# Zobo.net
KiCad netlist of a schematic drawn in EAGLE
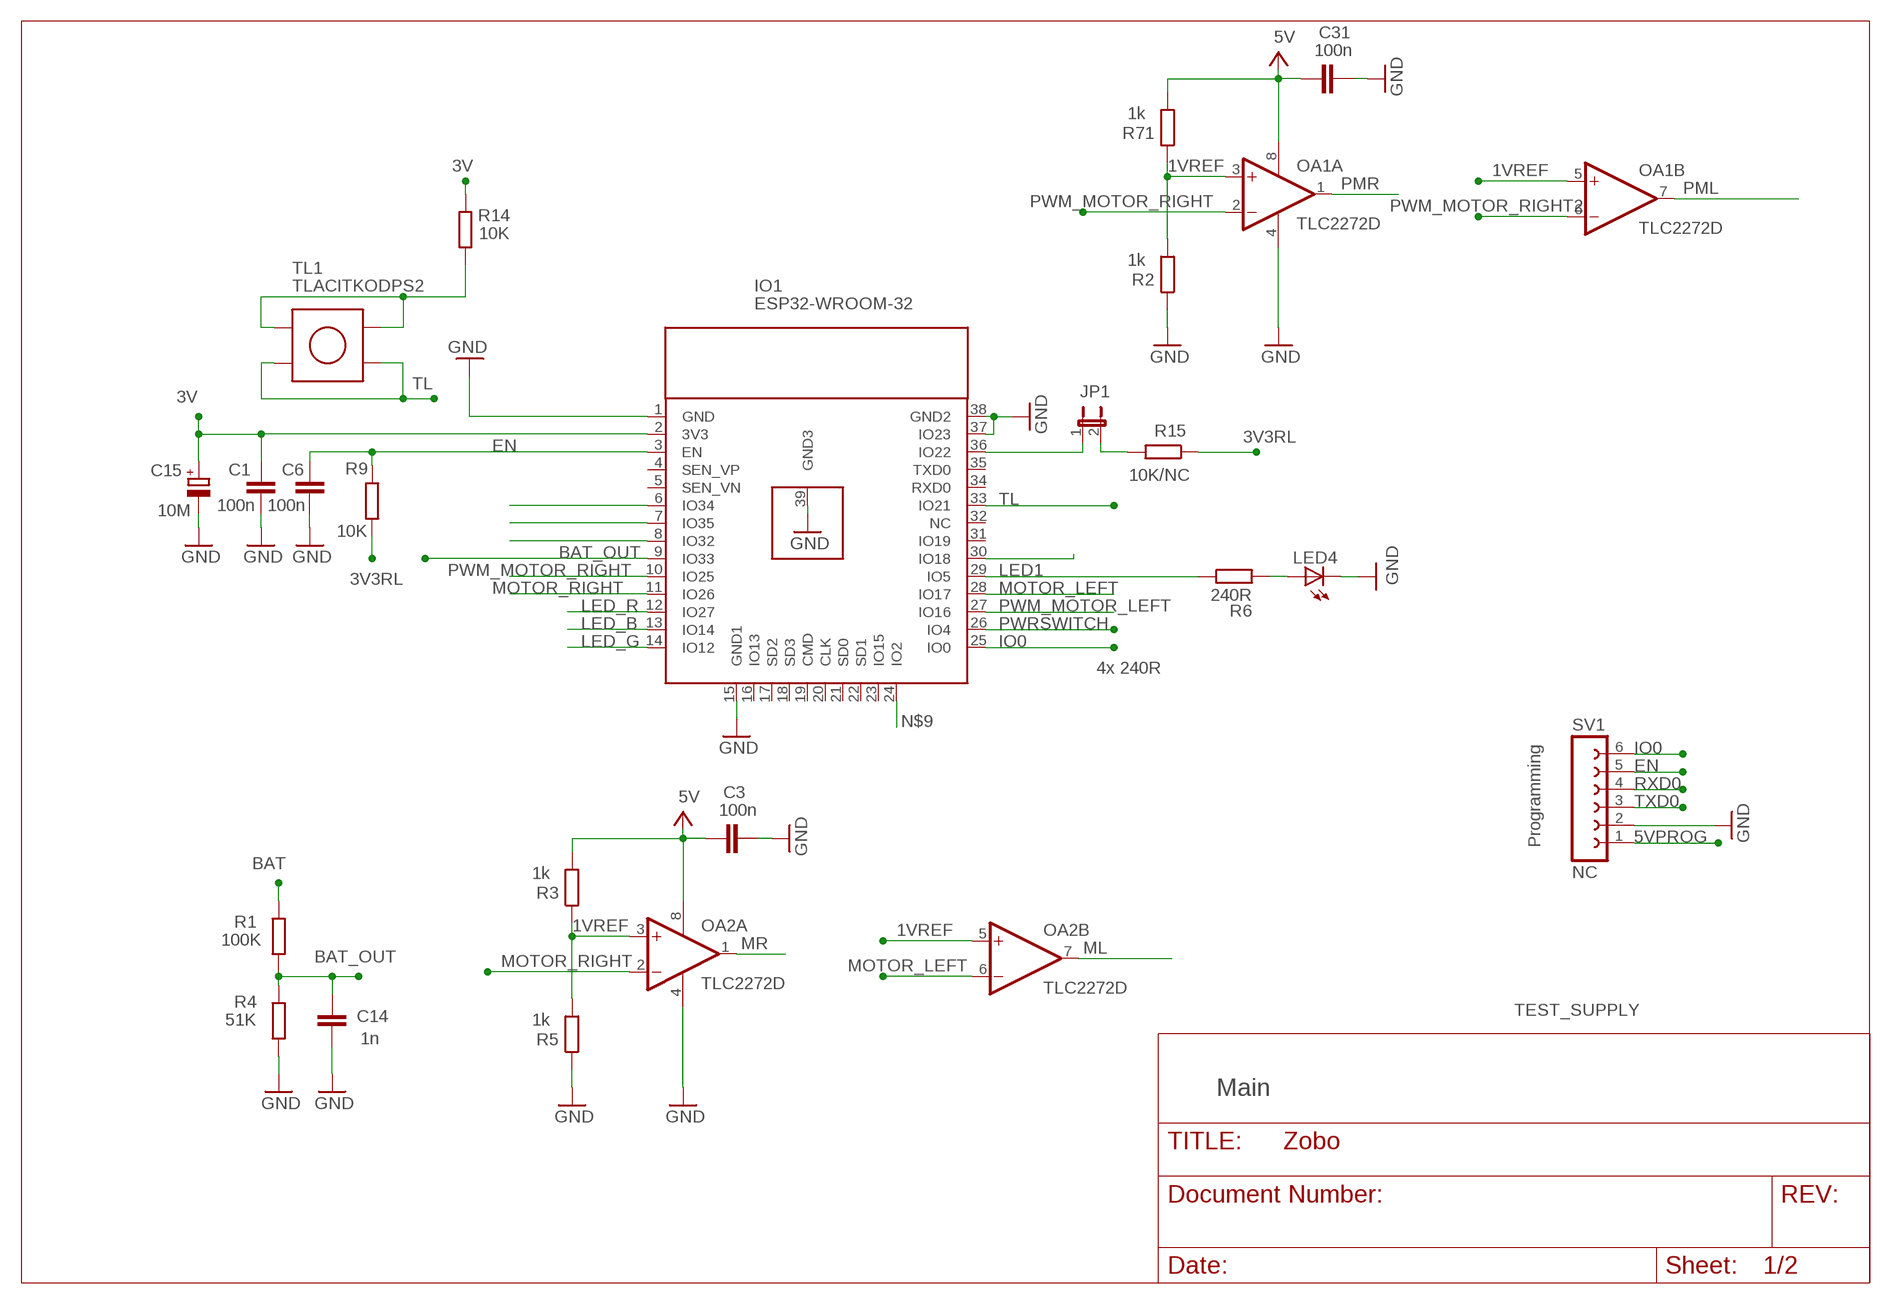
[diagram p0: schematic, sheet 1]
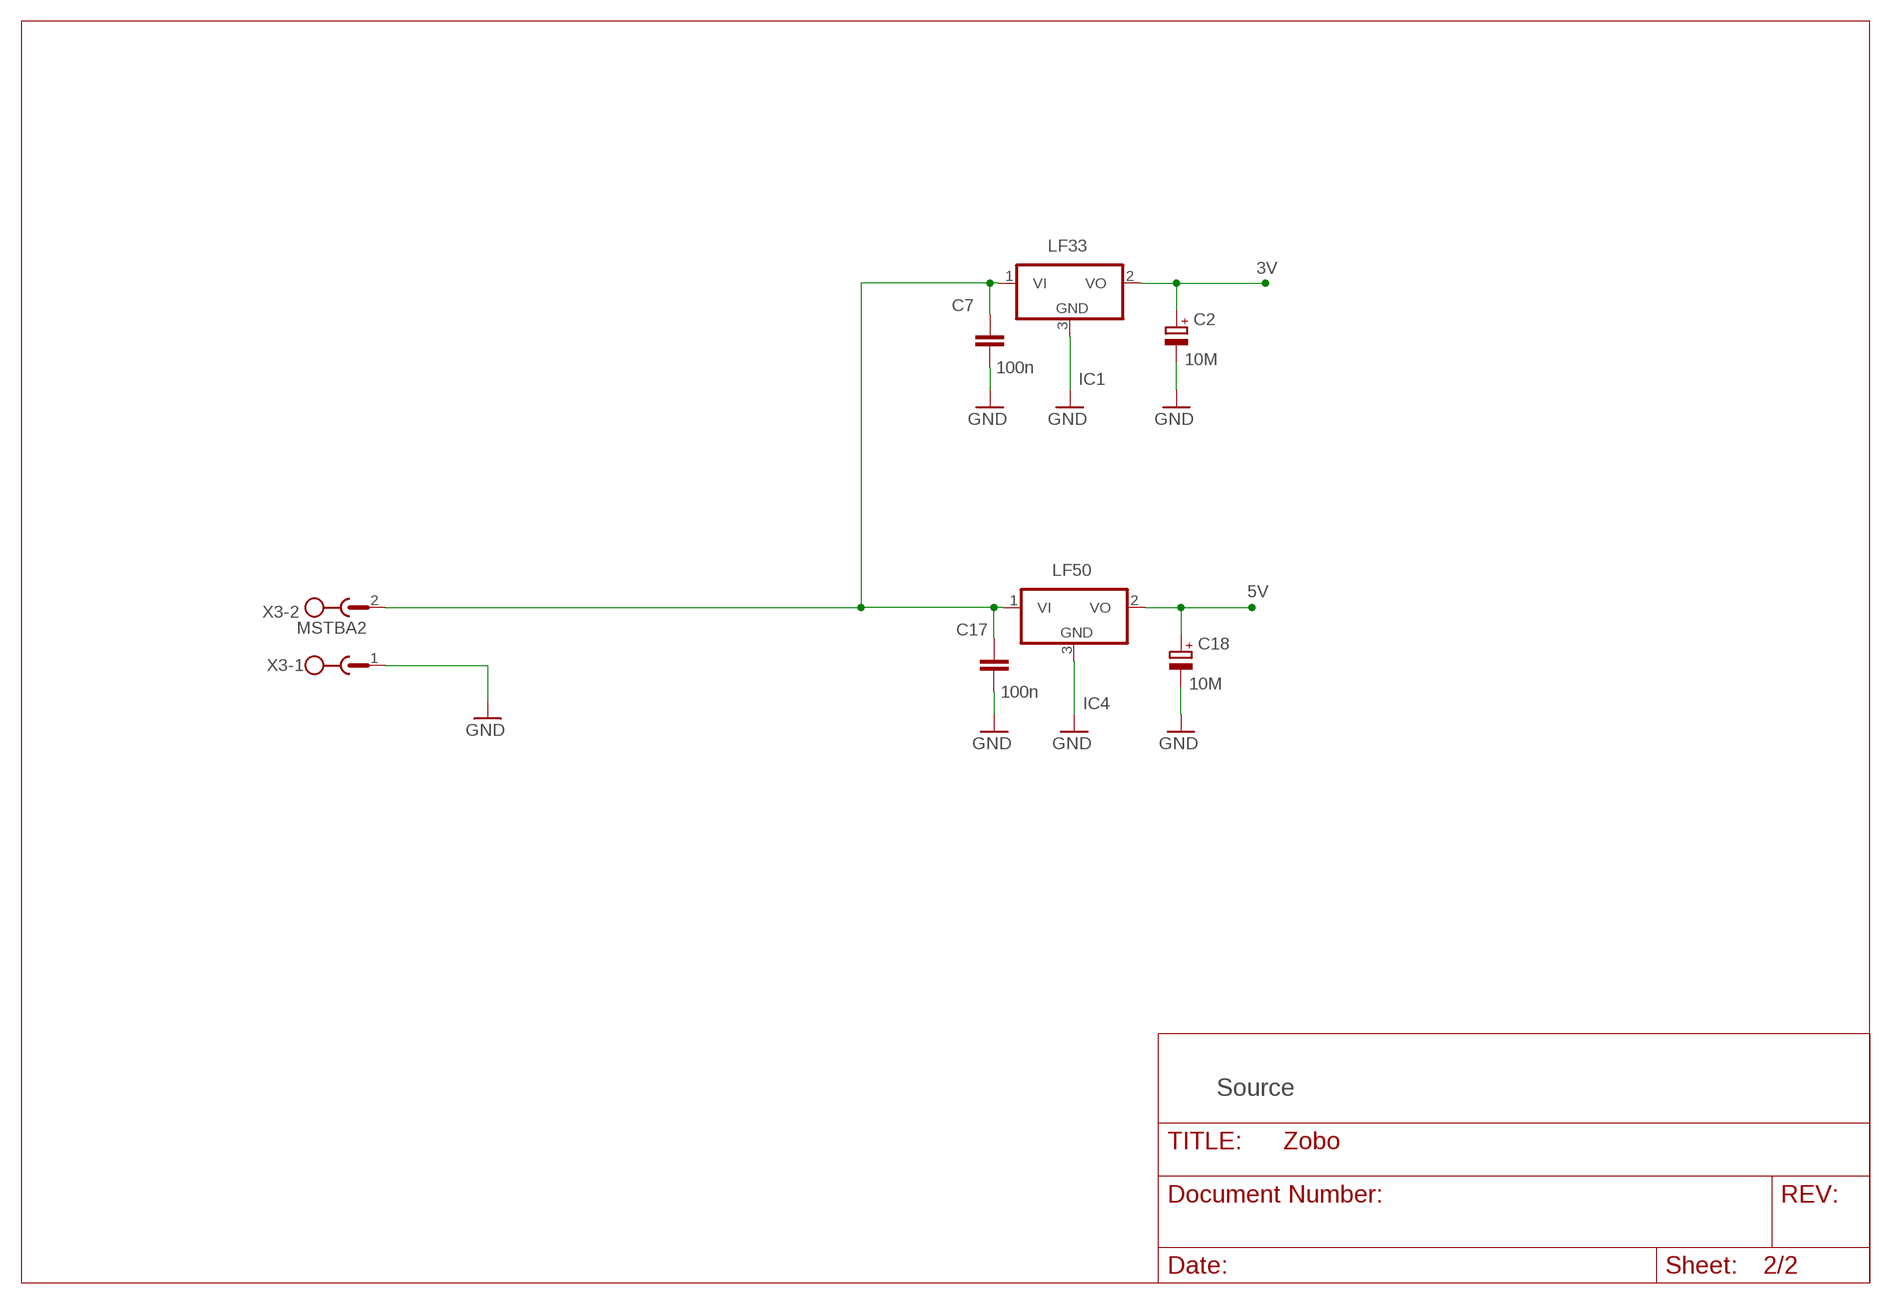
[diagram p1: schematic, sheet 2]

(export (version "E")
  (design (tool "Eeschema 10.0.6"))
  (components
    (comp (ref "C2")
      (value "10M")
      (footprint "eagle-import:CT3216")
      (libsource (lib "eagle-import") (part "CPOL-EUCT3216"))
    )
    (comp (ref "C7")
      (value "100n")
      (footprint "eagle-import:C0805")
      (libsource (lib "eagle-import") (part "C-EUC0805"))
    )
    (comp (ref "C17")
      (value "100n")
      (footprint "eagle-import:C0805")
      (libsource (lib "eagle-import") (part "C-EUC0805"))
    )
    (comp (ref "C18")
      (value "10M")
      (footprint "eagle-import:CT3216")
      (libsource (lib "eagle-import") (part "CPOL-EUCT3216"))
    )
    (comp (ref "IC1")
      (value "LF33")
      (footprint "eagle-import:TO252")
      (libsource (lib "eagle-import") (part "78DT05"))
    )
    (comp (ref "IC4")
      (value "LF50")
      (footprint "eagle-import:TO252")
      (libsource (lib "eagle-import") (part "78DT05"))
    )
    (comp (ref "X3")
      (value "MSTBA2")
      (footprint "eagle-import:MSTBA2")
      (fields (field (name "MF") "FARNELL") (field (name "MPN") "1757242"))
      (libsource (lib "eagle-import") (part "MSTBA2"))
    )
    (comp (ref "C1")
      (value "100n")
      (footprint "eagle-import:C0805")
      (libsource (lib "eagle-import") (part "C-EUC0805"))
    )
    (comp (ref "C3")
      (value "100n")
      (footprint "eagle-import:C0805")
      (libsource (lib "eagle-import") (part "rcl_TOM_C-EUC0805"))
    )
    (comp (ref "C6")
      (value "100n")
      (footprint "eagle-import:C0805")
      (libsource (lib "eagle-import") (part "C-EUC0805"))
    )
    (comp (ref "C14")
      (value "1n")
      (footprint "eagle-import:C0805")
      (libsource (lib "eagle-import") (part "C-EUC0805"))
    )
    (comp (ref "C15")
      (value "10M")
      (footprint "eagle-import:CT3216")
      (libsource (lib "eagle-import") (part "CPOL-EUCT3216"))
    )
    (comp (ref "C31")
      (value "100n")
      (footprint "eagle-import:C0805")
      (libsource (lib "eagle-import") (part "rcl_TOM_C-EUC0805"))
    )
    (comp (ref "IO1")
      (value "ESP32-WROOM-32")
      (footprint "eagle-import:ESP32-WROOM-32")
      (libsource (lib "eagle-import") (part "ESP32-WROOM-32"))
    )
    (comp (ref "JP1")
      (value "JP1E")
      (footprint "eagle-import:JP1")
      (libsource (lib "eagle-import") (part "JP1E"))
    )
    (comp (ref "LED4")
      (value "LEDCHIPLED_0805")
      (footprint "eagle-import:CHIPLED_0805")
      (libsource (lib "eagle-import") (part "LEDCHIPLED_0805"))
    )
    (comp (ref "OA1")
      (value "TLC2272D")
      (footprint "eagle-import:SO08")
      (libsource (lib "eagle-import") (part "TLC2272D"))
    )
    (comp (ref "OA2")
      (value "TLC2272D")
      (footprint "eagle-import:SO08")
      (libsource (lib "eagle-import") (part "TLC2272D"))
    )
    (comp (ref "R1")
      (value "100K")
      (footprint "eagle-import:R0805")
      (libsource (lib "eagle-import") (part "R-EU_R0805"))
    )
    (comp (ref "R2")
      (value "1k")
      (footprint "eagle-import:R0805")
      (libsource (lib "eagle-import") (part "R-EU_R0805"))
    )
    (comp (ref "R3")
      (value "1k")
      (footprint "eagle-import:R0805")
      (libsource (lib "eagle-import") (part "R-EU_R0805"))
    )
    (comp (ref "R4")
      (value "51K")
      (footprint "eagle-import:R0805")
      (libsource (lib "eagle-import") (part "R-EU_R0805"))
    )
    (comp (ref "R5")
      (value "1k")
      (footprint "eagle-import:R0805")
      (libsource (lib "eagle-import") (part "R-EU_R0805"))
    )
    (comp (ref "R6")
      (value "240R")
      (footprint "eagle-import:R0805")
      (libsource (lib "eagle-import") (part "R-EU_R0805"))
    )
    (comp (ref "R9")
      (value "10K")
      (footprint "eagle-import:R0805")
      (libsource (lib "eagle-import") (part "R-EU_R0805"))
    )
    (comp (ref "R14")
      (value "10K")
      (footprint "eagle-import:R0805")
      (libsource (lib "eagle-import") (part "R-EU_R0805"))
    )
    (comp (ref "R15")
      (value "10K/NC")
      (footprint "eagle-import:R0805")
      (libsource (lib "eagle-import") (part "R-EU_R0805"))
    )
    (comp (ref "R71")
      (value "1k")
      (footprint "eagle-import:R0805")
      (libsource (lib "eagle-import") (part "R-EU_R0805"))
    )
    (comp (ref "SV1")
      (value "NC")
      (footprint "eagle-import:FE06")
      (libsource (lib "eagle-import") (part "FE06-1R"))
    )
    (comp (ref "TL1")
      (value "TLACITKODPS2")
      (footprint "eagle-import:TLACITKO_DPS2")
      (libsource (lib "eagle-import") (part "TLACITKO?DPS2"))
    )
  )
  (nets
    (net (code "1") (name "1VREF") (class "Default")
      (node (ref "OA1") (pin "3") (pinfunction "+IN_3") (pintype "input"))
      (node (ref "OA1") (pin "5") (pinfunction "+IN_5") (pintype "input"))
      (node (ref "OA2") (pin "3") (pinfunction "+IN_3") (pintype "input"))
      (node (ref "OA2") (pin "5") (pinfunction "+IN_5") (pintype "input"))
      (node (ref "R2") (pin "2") (pinfunction "2_2") (pintype "passive"))
      (node (ref "R3") (pin "1") (pinfunction "1_1") (pintype "passive"))
      (node (ref "R5") (pin "2") (pinfunction "2_2") (pintype "passive"))
      (node (ref "R71") (pin "1") (pinfunction "1_1") (pintype "passive"))
    )
    (net (code "2") (name "3V") (class "Default")
      (node (ref "C1") (pin "2") (pinfunction "2_2") (pintype "passive"))
      (node (ref "C15") (pin "+") (pinfunction "+_+") (pintype "passive"))
      (node (ref "C2") (pin "+") (pinfunction "+_+") (pintype "passive"))
      (node (ref "IC1") (pin "2") (pinfunction "VO_2") (pintype "passive"))
      (node (ref "IO1") (pin "2") (pinfunction "3V3_2") (pintype "passive"))
      (node (ref "R14") (pin "2") (pinfunction "2_2") (pintype "passive"))
    )
    (net (code "3") (name "3V3RL") (class "Default")
      (node (ref "R15") (pin "1") (pinfunction "1_1") (pintype "passive"))
      (node (ref "R9") (pin "2") (pinfunction "2_2") (pintype "passive"))
    )
    (net (code "4") (name "5V") (class "Default")
      (node (ref "C18") (pin "+") (pinfunction "+_+") (pintype "passive"))
      (node (ref "C3") (pin "1") (pinfunction "1_1") (pintype "passive"))
      (node (ref "C31") (pin "1") (pinfunction "1_1") (pintype "passive"))
      (node (ref "IC4") (pin "2") (pinfunction "VO_2") (pintype "passive"))
      (node (ref "OA1") (pin "8") (pinfunction "V+_8") (pintype "power_in"))
      (node (ref "OA2") (pin "8") (pinfunction "V+_8") (pintype "power_in"))
      (node (ref "R3") (pin "2") (pinfunction "2_2") (pintype "passive"))
      (node (ref "R71") (pin "2") (pinfunction "2_2") (pintype "passive"))
    )
    (net (code "5") (name "5VPROG") (class "Default")
      (node (ref "SV1") (pin "1") (pinfunction "1_1") (pintype "passive"))
    )
    (net (code "6") (name "BAT") (class "Default")
      (node (ref "C17") (pin "2") (pinfunction "2_2") (pintype "passive"))
      (node (ref "C7") (pin "2") (pinfunction "2_2") (pintype "passive"))
      (node (ref "IC1") (pin "1") (pinfunction "VI_1") (pintype "input"))
      (node (ref "IC4") (pin "1") (pinfunction "VI_1") (pintype "input"))
      (node (ref "R1") (pin "1") (pinfunction "1_1") (pintype "passive"))
      (node (ref "X3") (pin "2") (pinfunction "1_2") (pintype "passive"))
    )
    (net (code "7") (name "BAT_OUT") (class "Default")
      (node (ref "C14") (pin "2") (pinfunction "2_2") (pintype "passive"))
      (node (ref "IO1") (pin "9") (pinfunction "IO33_9") (pintype "passive"))
      (node (ref "R1") (pin "2") (pinfunction "2_2") (pintype "passive"))
      (node (ref "R4") (pin "1") (pinfunction "1_1") (pintype "passive"))
    )
    (net (code "8") (name "EN") (class "Default")
      (node (ref "C6") (pin "2") (pinfunction "2_2") (pintype "passive"))
      (node (ref "IO1") (pin "3") (pinfunction "EN_3") (pintype "passive"))
      (node (ref "R9") (pin "1") (pinfunction "1_1") (pintype "passive"))
      (node (ref "SV1") (pin "5") (pinfunction "5_5") (pintype "passive"))
    )
    (net (code "9") (name "GND") (class "Default")
      (node (ref "C1") (pin "1") (pinfunction "1_1") (pintype "passive"))
      (node (ref "C14") (pin "1") (pinfunction "1_1") (pintype "passive"))
      (node (ref "C15") (pin "-") (pinfunction "-_-") (pintype "passive"))
      (node (ref "C17") (pin "1") (pinfunction "1_1") (pintype "passive"))
      (node (ref "C18") (pin "-") (pinfunction "-_-") (pintype "passive"))
      (node (ref "C2") (pin "-") (pinfunction "-_-") (pintype "passive"))
      (node (ref "C3") (pin "2") (pinfunction "2_2") (pintype "passive"))
      (node (ref "C31") (pin "2") (pinfunction "2_2") (pintype "passive"))
      (node (ref "C6") (pin "1") (pinfunction "1_1") (pintype "passive"))
      (node (ref "C7") (pin "1") (pinfunction "1_1") (pintype "passive"))
      (node (ref "IC1") (pin "3") (pinfunction "GND_3") (pintype "passive"))
      (node (ref "IC4") (pin "3") (pinfunction "GND_3") (pintype "passive"))
      (node (ref "IO1") (pin "1") (pinfunction "GND_1") (pintype "passive"))
      (node (ref "IO1") (pin "15") (pinfunction "GND1_15") (pintype "passive"))
      (node (ref "IO1") (pin "37") (pinfunction "IO23_37") (pintype "passive"))
      (node (ref "IO1") (pin "38") (pinfunction "GND2_38") (pintype "passive"))
      (node (ref "IO1") (pin "39") (pinfunction "GND3_39") (pintype "passive"))
      (node (ref "LED4") (pin "C") (pinfunction "C_C") (pintype "passive"))
      (node (ref "OA1") (pin "4") (pinfunction "V-_4") (pintype "power_in"))
      (node (ref "OA2") (pin "4") (pinfunction "V-_4") (pintype "power_in"))
      (node (ref "R2") (pin "1") (pinfunction "1_1") (pintype "passive"))
      (node (ref "R4") (pin "2") (pinfunction "2_2") (pintype "passive"))
      (node (ref "R5") (pin "1") (pinfunction "1_1") (pintype "passive"))
      (node (ref "SV1") (pin "2") (pinfunction "2_2") (pintype "passive"))
      (node (ref "X3") (pin "1") (pinfunction "1_1") (pintype "passive"))
    )
    (net (code "10") (name "IO0") (class "Default")
      (node (ref "IO1") (pin "25") (pinfunction "IO0_25") (pintype "passive"))
      (node (ref "SV1") (pin "6") (pinfunction "6_6") (pintype "passive"))
    )
    (net (code "11") (name "LED1") (class "Default")
      (node (ref "IO1") (pin "29") (pinfunction "IO5_29") (pintype "passive"))
      (node (ref "R6") (pin "1") (pinfunction "1_1") (pintype "passive"))
    )
    (net (code "12") (name "LED_B") (class "Default")
      (node (ref "IO1") (pin "13") (pinfunction "IO14_13") (pintype "passive"))
    )
    (net (code "13") (name "LED_G") (class "Default")
      (node (ref "IO1") (pin "14") (pinfunction "IO12_14") (pintype "passive"))
    )
    (net (code "14") (name "LED_R") (class "Default")
      (node (ref "IO1") (pin "12") (pinfunction "IO27_12") (pintype "passive"))
    )
    (net (code "15") (name "ML") (class "Default")
      (node (ref "OA2") (pin "7") (pinfunction "OUT_7") (pintype "output"))
    )
    (net (code "16") (name "MOTOR_LEFT") (class "Default")
      (node (ref "IO1") (pin "28") (pinfunction "IO17_28") (pintype "passive"))
      (node (ref "OA2") (pin "6") (pinfunction "-IN_6") (pintype "input"))
    )
    (net (code "17") (name "MOTOR_RIGHT") (class "Default")
      (node (ref "IO1") (pin "11") (pinfunction "IO26_11") (pintype "passive"))
      (node (ref "OA2") (pin "2") (pinfunction "-IN_2") (pintype "input"))
    )
    (net (code "18") (name "MR") (class "Default")
      (node (ref "OA2") (pin "1") (pinfunction "OUT_1") (pintype "output"))
    )
    (net (code "19") (name "N$9") (class "Default")
      (node (ref "IO1") (pin "24") (pinfunction "IO2_24") (pintype "passive"))
    )
    (net (code "20") (name "Net-(IO1-IO22)") (class "Default")
      (node (ref "IO1") (pin "36") (pinfunction "IO22_36") (pintype "passive"))
      (node (ref "JP1") (pin "1") (pinfunction "1_1") (pintype "passive"))
    )
    (net (code "21") (name "Net-(JP1-Pad2)") (class "Default")
      (node (ref "JP1") (pin "2") (pinfunction "2_2") (pintype "passive"))
      (node (ref "R15") (pin "2") (pinfunction "2_2") (pintype "passive"))
    )
    (net (code "22") (name "Net-(LED4-PadA)") (class "Default")
      (node (ref "LED4") (pin "A") (pinfunction "A_A") (pintype "passive"))
      (node (ref "R6") (pin "2") (pinfunction "2_2") (pintype "passive"))
    )
    (net (code "23") (name "Net-(R14-Pad1)") (class "Default")
      (node (ref "R14") (pin "1") (pinfunction "1_1") (pintype "passive"))
      (node (ref "TL1") (pin "1") (pinfunction "1_1") (pintype "passive"))
      (node (ref "TL1") (pin "2") (pinfunction "2_2") (pintype "passive"))
    )
    (net (code "24") (name "PML") (class "Default")
      (node (ref "OA1") (pin "7") (pinfunction "OUT_7") (pintype "output"))
    )
    (net (code "25") (name "PMR") (class "Default")
      (node (ref "OA1") (pin "1") (pinfunction "OUT_1") (pintype "output"))
    )
    (net (code "26") (name "PWM_MOTOR_LEFT") (class "Default")
      (node (ref "IO1") (pin "27") (pinfunction "IO16_27") (pintype "passive"))
    )
    (net (code "27") (name "PWM_MOTOR_RIGHT") (class "Default")
      (node (ref "IO1") (pin "10") (pinfunction "IO25_10") (pintype "passive"))
      (node (ref "OA1") (pin "2") (pinfunction "-IN_2") (pintype "input"))
    )
    (net (code "28") (name "PWM_MOTOR_RIGHT2") (class "Default")
      (node (ref "OA1") (pin "6") (pinfunction "-IN_6") (pintype "input"))
    )
    (net (code "29") (name "PWRSWITCH") (class "Default")
      (node (ref "IO1") (pin "26") (pinfunction "IO4_26") (pintype "passive"))
    )
    (net (code "30") (name "RXD0") (class "Default")
      (node (ref "SV1") (pin "4") (pinfunction "4_4") (pintype "passive"))
    )
    (net (code "31") (name "TL") (class "Default")
      (node (ref "IO1") (pin "33") (pinfunction "IO21_33") (pintype "passive"))
      (node (ref "TL1") (pin "3") (pinfunction "3_3") (pintype "passive"))
      (node (ref "TL1") (pin "4") (pinfunction "4_4") (pintype "passive"))
    )
    (net (code "32") (name "TXD0") (class "Default")
      (node (ref "SV1") (pin "3") (pinfunction "3_3") (pintype "passive"))
    )
    (net (code "33") (name "unconnected-(IO1-CLK-Pad20)") (class "Default")
      (node (ref "IO1") (pin "20") (pinfunction "CLK_20") (pintype "passive"))
    )
    (net (code "34") (name "unconnected-(IO1-CMD-Pad19)") (class "Default")
      (node (ref "IO1") (pin "19") (pinfunction "CMD_19") (pintype "passive"))
    )
    (net (code "35") (name "unconnected-(IO1-IO13-Pad16)") (class "Default")
      (node (ref "IO1") (pin "16") (pinfunction "IO13_16") (pintype "passive"))
    )
    (net (code "36") (name "unconnected-(IO1-IO15-Pad23)") (class "Default")
      (node (ref "IO1") (pin "23") (pinfunction "IO15_23") (pintype "passive"))
    )
    (net (code "37") (name "unconnected-(IO1-IO18-Pad30)") (class "Default")
      (node (ref "IO1") (pin "30") (pinfunction "IO18_30") (pintype "passive"))
    )
    (net (code "38") (name "unconnected-(IO1-IO19-Pad31)") (class "Default")
      (node (ref "IO1") (pin "31") (pinfunction "IO19_31") (pintype "passive"))
    )
    (net (code "39") (name "unconnected-(IO1-IO32-Pad8)") (class "Default")
      (node (ref "IO1") (pin "8") (pinfunction "IO32_8") (pintype "passive"))
    )
    (net (code "40") (name "unconnected-(IO1-IO34-Pad6)") (class "Default")
      (node (ref "IO1") (pin "6") (pinfunction "IO34_6") (pintype "passive"))
    )
    (net (code "41") (name "unconnected-(IO1-IO35-Pad7)") (class "Default")
      (node (ref "IO1") (pin "7") (pinfunction "IO35_7") (pintype "passive"))
    )
    (net (code "42") (name "unconnected-(IO1-NC-Pad32)") (class "Default")
      (node (ref "IO1") (pin "32") (pinfunction "NC_32") (pintype "passive"))
    )
    (net (code "43") (name "unconnected-(IO1-RXD0-Pad34)") (class "Default")
      (node (ref "IO1") (pin "34") (pinfunction "RXD0_34") (pintype "passive"))
    )
    (net (code "44") (name "unconnected-(IO1-SD0-Pad21)") (class "Default")
      (node (ref "IO1") (pin "21") (pinfunction "SD0_21") (pintype "passive"))
    )
    (net (code "45") (name "unconnected-(IO1-SD1-Pad22)") (class "Default")
      (node (ref "IO1") (pin "22") (pinfunction "SD1_22") (pintype "passive"))
    )
    (net (code "46") (name "unconnected-(IO1-SD2-Pad17)") (class "Default")
      (node (ref "IO1") (pin "17") (pinfunction "SD2_17") (pintype "passive"))
    )
    (net (code "47") (name "unconnected-(IO1-SD3-Pad18)") (class "Default")
      (node (ref "IO1") (pin "18") (pinfunction "SD3_18") (pintype "passive"))
    )
    (net (code "48") (name "unconnected-(IO1-SEN_VN-Pad5)") (class "Default")
      (node (ref "IO1") (pin "5") (pinfunction "SEN_VN_5") (pintype "passive"))
    )
    (net (code "49") (name "unconnected-(IO1-SEN_VP-Pad4)") (class "Default")
      (node (ref "IO1") (pin "4") (pinfunction "SEN_VP_4") (pintype "passive"))
    )
    (net (code "50") (name "unconnected-(IO1-TXD0-Pad35)") (class "Default")
      (node (ref "IO1") (pin "35") (pinfunction "TXD0_35") (pintype "passive"))
    )
  )
)
